# DIS06043H-ESP32-V2_020231204.net
KiCad netlist of a schematic drawn in EAGLE
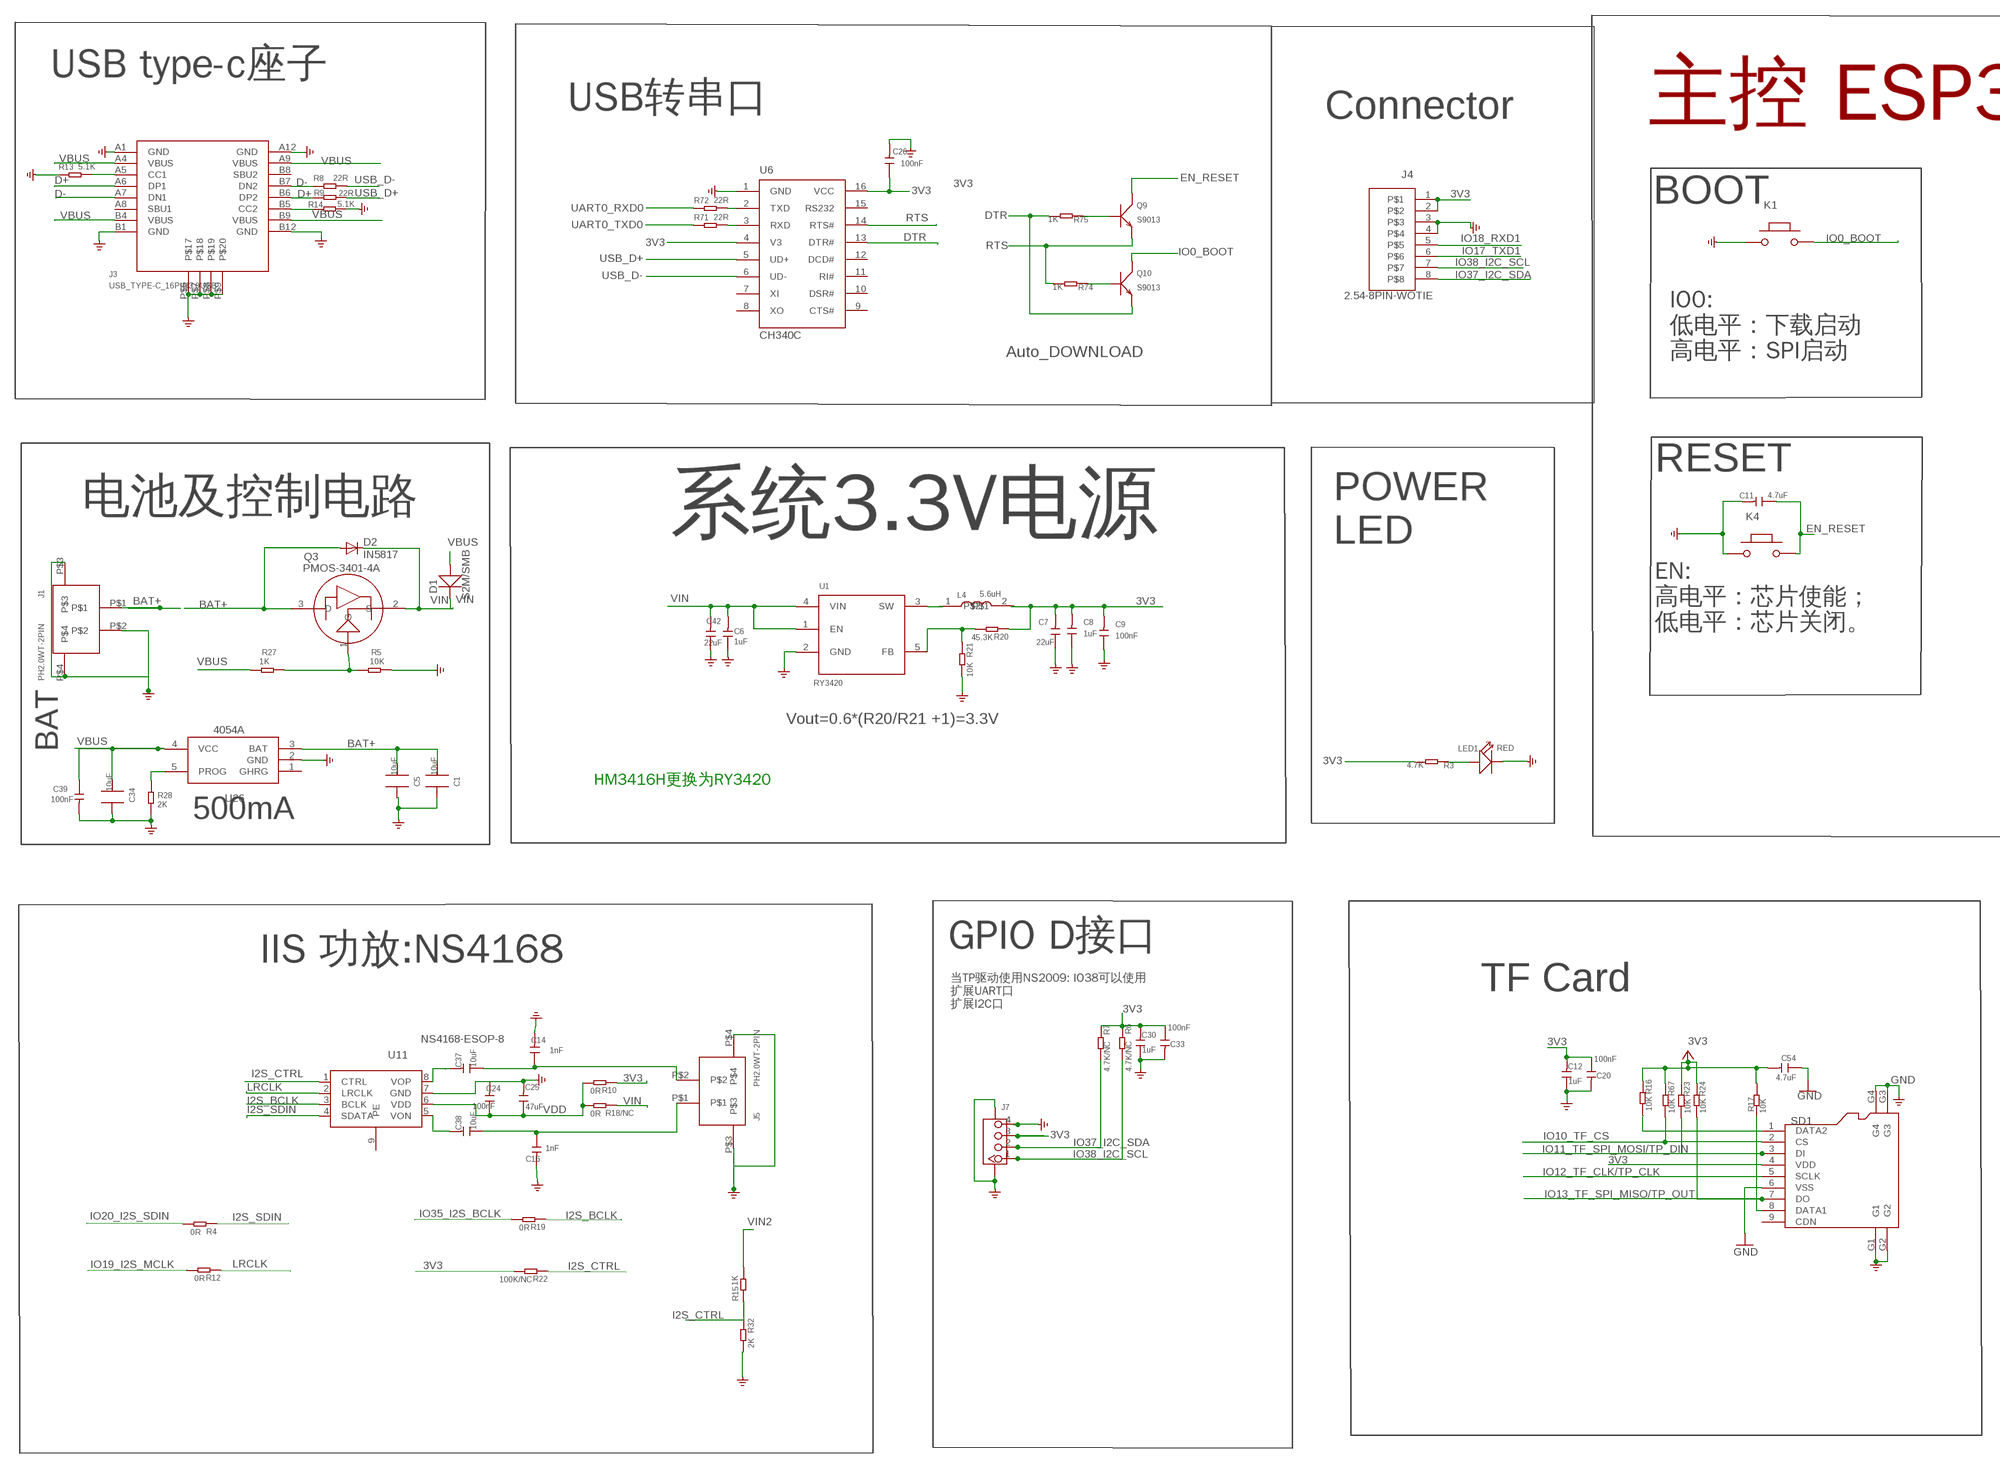
[diagram p0: schematic, sheet 1, part 1 of 2]
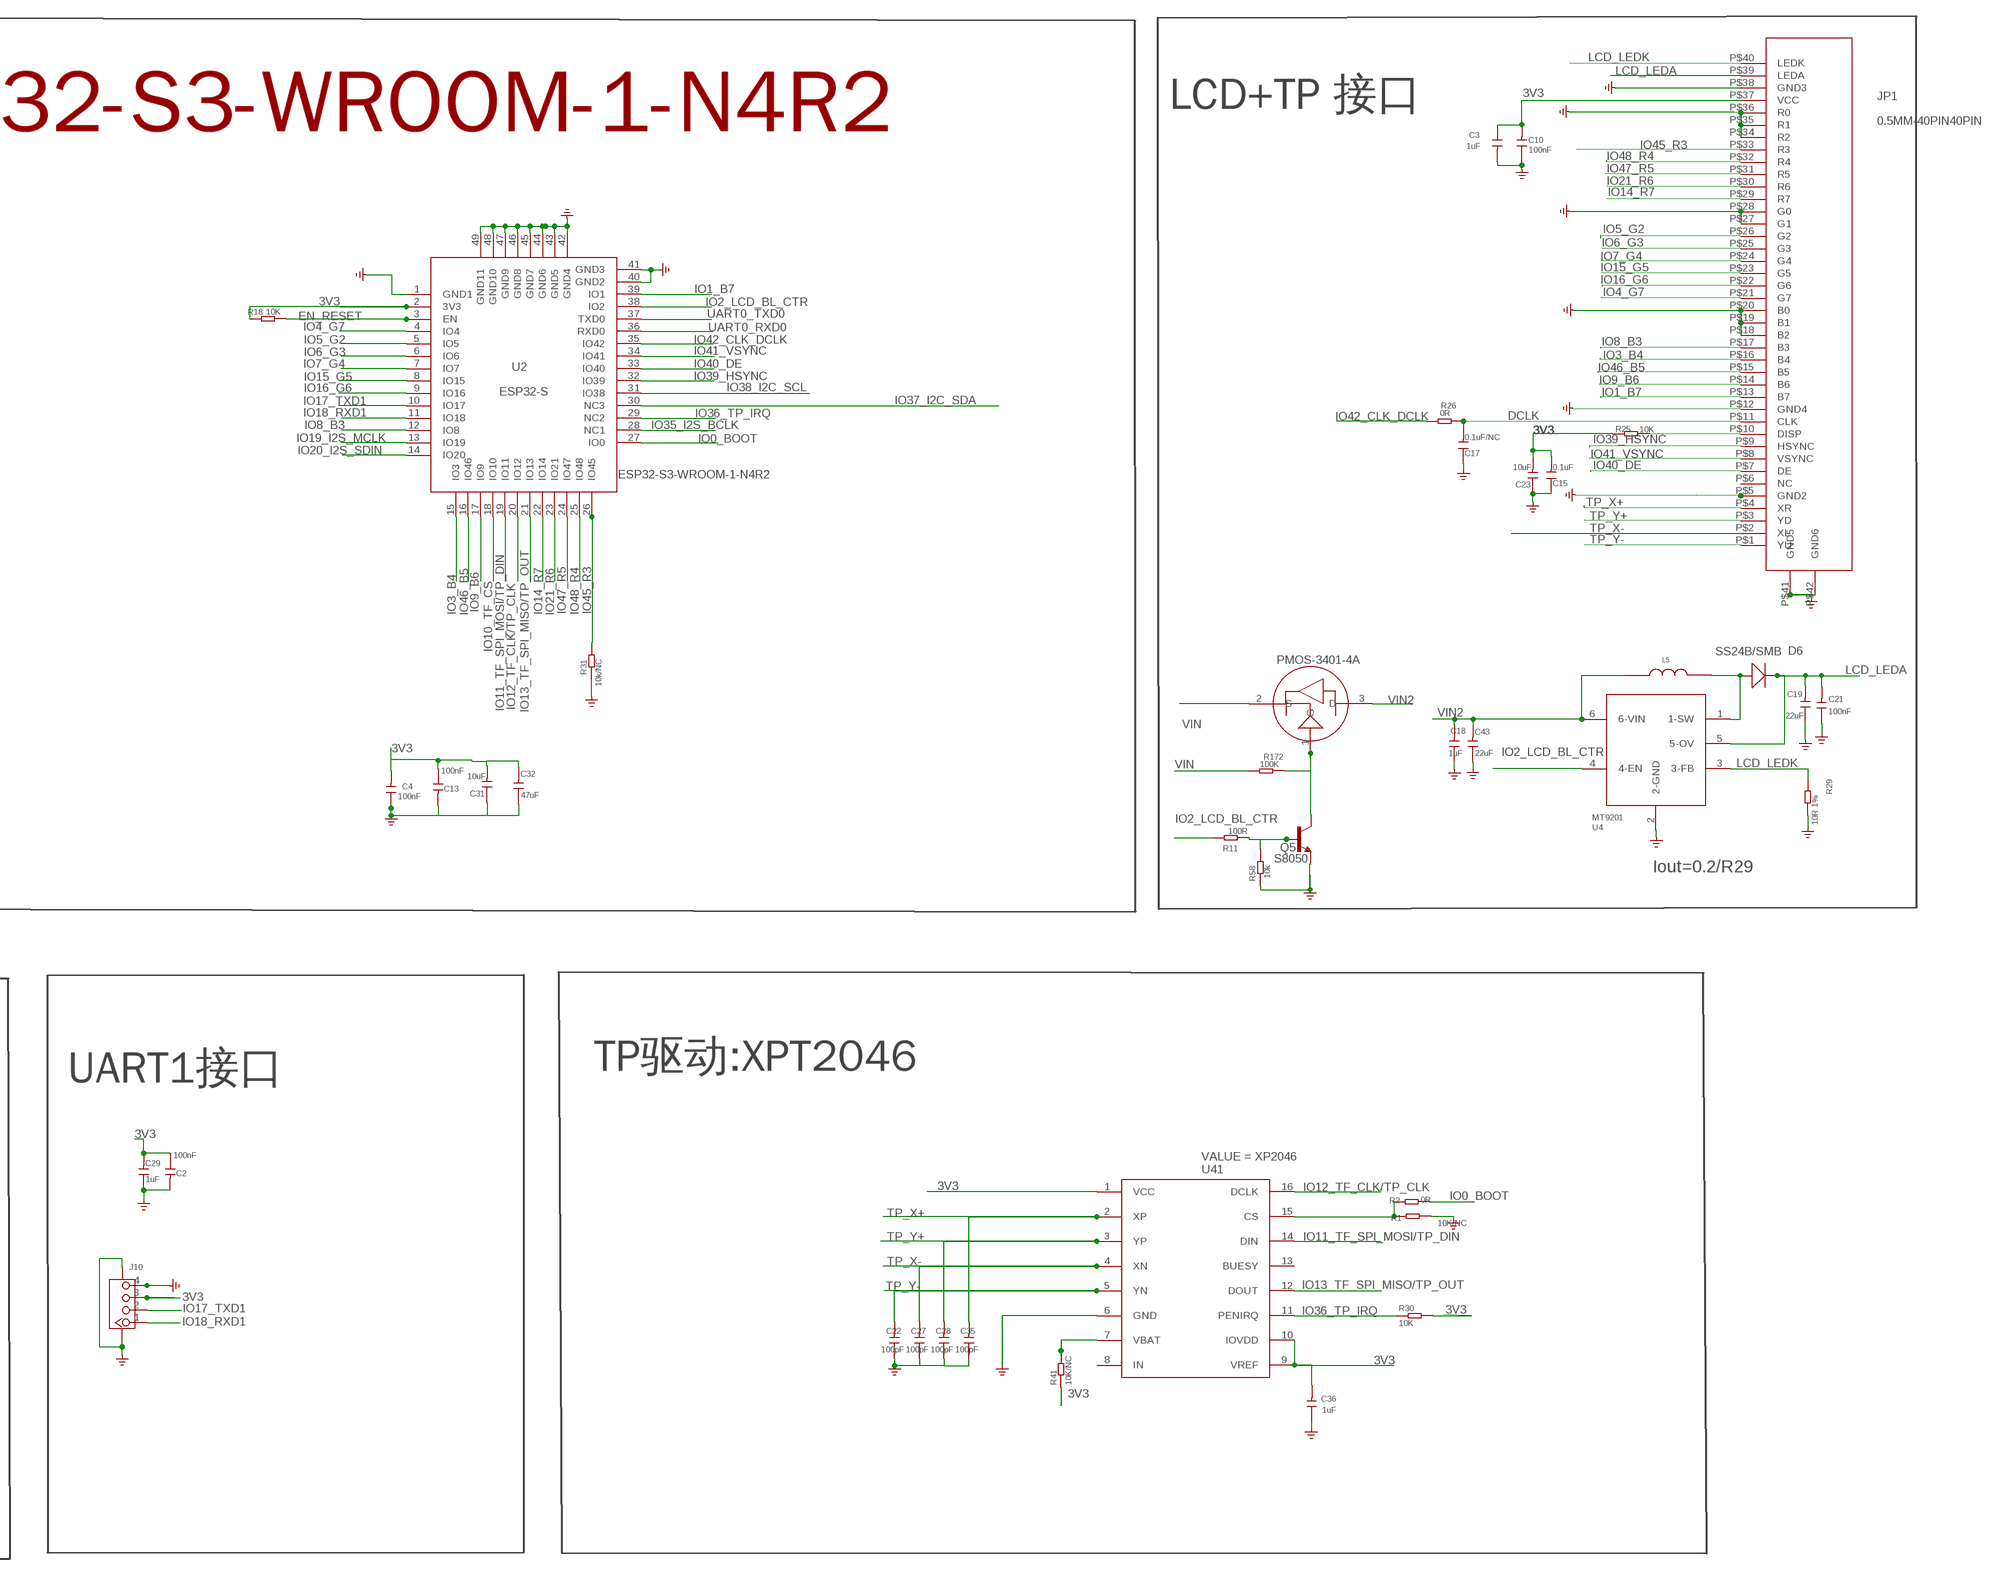
[diagram p1: schematic, sheet 1, part 2 of 2]

(export (version "E")
  (design (tool "Eeschema 10.0.6"))
  (components
    (comp (ref "C1")
      (value "10uF")
      (footprint "eagle-import:0805_S")
      (libsource (lib "eagle-import") (part "C0805_S"))
    )
    (comp (ref "C2")
      (value "100nF")
      (footprint "eagle-import:C0603")
      (libsource (lib "eagle-import") (part "C-0603"))
    )
    (comp (ref "C3")
      (value "1uF")
      (footprint "eagle-import:C0603")
      (libsource (lib "eagle-import") (part "C-0603"))
    )
    (comp (ref "C4")
      (value "100nF")
      (footprint "eagle-import:C0603")
      (libsource (lib "eagle-import") (part "C-0603"))
    )
    (comp (ref "C5")
      (value "10uF")
      (footprint "eagle-import:0805_S")
      (libsource (lib "eagle-import") (part "C0805_S"))
    )
    (comp (ref "C6")
      (value "1uF")
      (footprint "eagle-import:0603")
      (libsource (lib "eagle-import") (part "C0603"))
    )
    (comp (ref "C7")
      (value "22uF")
      (footprint "eagle-import:0805")
      (libsource (lib "eagle-import") (part "C0805"))
    )
    (comp (ref "C8")
      (value "1uF")
      (footprint "eagle-import:0603")
      (libsource (lib "eagle-import") (part "C0603"))
    )
    (comp (ref "C9")
      (value "100nF")
      (footprint "eagle-import:0603")
      (libsource (lib "eagle-import") (part "C0603"))
    )
    (comp (ref "C10")
      (value "100nF")
      (footprint "eagle-import:C0603")
      (libsource (lib "eagle-import") (part "C-0603"))
    )
    (comp (ref "C11")
      (value "4.7uF")
      (footprint "eagle-import:0603")
      (libsource (lib "eagle-import") (part "C0603"))
    )
    (comp (ref "C12")
      (value "1uF")
      (footprint "eagle-import:DISCRETE_C0603")
      (libsource (lib "eagle-import") (part "A_xbj_DISCRETE_C-0603"))
    )
    (comp (ref "C13")
      (value "100nF")
      (footprint "eagle-import:C0603")
      (libsource (lib "eagle-import") (part "C-0603"))
    )
    (comp (ref "C14")
      (value "1nF")
      (footprint "eagle-import:C0603")
      (libsource (lib "eagle-import") (part "C-0603"))
    )
    (comp (ref "C15")
      (value "0.1uF")
      (footprint "eagle-import:DISCRETE_C0603")
      (libsource (lib "eagle-import") (part "DISCRETE_C-0603"))
    )
    (comp (ref "C16")
      (value "1nF")
      (footprint "eagle-import:C0603")
      (libsource (lib "eagle-import") (part "C-0603"))
    )
    (comp (ref "C17")
      (value "0.1uF/NC")
      (footprint "eagle-import:DISCRETE_C0603")
      (libsource (lib "eagle-import") (part "DISCRETE_C-0603"))
    )
    (comp (ref "C18")
      (value "1uF")
      (footprint "eagle-import:0603")
      (libsource (lib "eagle-import") (part "C0603"))
    )
    (comp (ref "C19")
      (value "22uF")
      (footprint "eagle-import:0805")
      (libsource (lib "eagle-import") (part "C0805"))
    )
    (comp (ref "C20")
      (value "100nF")
      (footprint "eagle-import:C0603")
      (libsource (lib "eagle-import") (part "C-0603"))
    )
    (comp (ref "C21")
      (value "100nF")
      (footprint "eagle-import:0603")
      (libsource (lib "eagle-import") (part "C0603"))
    )
    (comp (ref "C22")
      (value "100pF")
      (footprint "eagle-import:0603")
      (libsource (lib "eagle-import") (part "C0603"))
    )
    (comp (ref "C23")
      (value "10uF")
      (footprint "eagle-import:DISCRETE_C0603")
      (libsource (lib "eagle-import") (part "DISCRETE_C-0603"))
    )
    (comp (ref "C24")
      (value "100nF")
      (footprint "eagle-import:C0603")
      (libsource (lib "eagle-import") (part "C-0603"))
    )
    (comp (ref "C25")
      (value "47uF")
      (footprint "eagle-import:0805")
      (libsource (lib "eagle-import") (part "C0805"))
    )
    (comp (ref "C26")
      (value "100nF")
      (footprint "eagle-import:0603")
      (libsource (lib "eagle-import") (part "C0603"))
    )
    (comp (ref "C27")
      (value "100pF")
      (footprint "eagle-import:0603")
      (libsource (lib "eagle-import") (part "C0603"))
    )
    (comp (ref "C28")
      (value "100pF")
      (footprint "eagle-import:0603")
      (libsource (lib "eagle-import") (part "C0603"))
    )
    (comp (ref "C29")
      (value "1uF")
      (footprint "eagle-import:DISCRETE_C0603")
      (libsource (lib "eagle-import") (part "A_xbj_DISCRETE_C-0603"))
    )
    (comp (ref "C30")
      (value "1uF")
      (footprint "eagle-import:DISCRETE_C0603")
      (libsource (lib "eagle-import") (part "A_xbj_DISCRETE_C-0603"))
    )
    (comp (ref "C31")
      (value "10uF")
      (footprint "eagle-import:DISCRETE_C0603")
      (libsource (lib "eagle-import") (part "DISCRETE_C-0603"))
    )
    (comp (ref "C32")
      (value "47uF")
      (footprint "eagle-import:0805")
      (libsource (lib "eagle-import") (part "C0805"))
    )
    (comp (ref "C33")
      (value "100nF")
      (footprint "eagle-import:C0603")
      (libsource (lib "eagle-import") (part "C-0603"))
    )
    (comp (ref "C34")
      (value "10uF")
      (footprint "eagle-import:0805_S")
      (libsource (lib "eagle-import") (part "C0805_S"))
    )
    (comp (ref "C35")
      (value "100pF")
      (footprint "eagle-import:0603")
      (libsource (lib "eagle-import") (part "C0603"))
    )
    (comp (ref "C36")
      (value "1uF")
      (footprint "eagle-import:DISCRETE_C0603")
      (libsource (lib "eagle-import") (part "A_xbj_DISCRETE_C-0603"))
    )
    (comp (ref "C37")
      (value "10uF")
      (footprint "eagle-import:DISCRETE_C0603")
      (libsource (lib "eagle-import") (part "A_xbj_DISCRETE_C-0603"))
    )
    (comp (ref "C38")
      (value "10uF")
      (footprint "eagle-import:DISCRETE_C0603")
      (libsource (lib "eagle-import") (part "A_xbj_DISCRETE_C-0603"))
    )
    (comp (ref "C39")
      (value "100nF")
      (footprint "eagle-import:C0603")
      (libsource (lib "eagle-import") (part "C-0603"))
    )
    (comp (ref "C42")
      (value "22uF")
      (footprint "eagle-import:0805")
      (libsource (lib "eagle-import") (part "C0805"))
    )
    (comp (ref "C43")
      (value "22uF")
      (footprint "eagle-import:0805")
      (libsource (lib "eagle-import") (part "C0805"))
    )
    (comp (ref "C54")
      (value "4.7uF")
      (footprint "eagle-import:DISCRETE_C0603")
      (libsource (lib "eagle-import") (part "DISCRETE_C-0603"))
    )
    (comp (ref "D1")
      (value "S2M/SMB")
      (footprint "eagle-import:214AB")
      (libsource (lib "eagle-import") (part "214ABDO-214AB"))
    )
    (comp (ref "D2")
      (value "IN5817")
      (footprint "eagle-import:DO-214AC")
      (libsource (lib "eagle-import") (part "DIODE-DO-214AC"))
    )
    (comp (ref "D6")
      (value "SS24B/SMB")
      (footprint "eagle-import:214AB")
      (libsource (lib "eagle-import") (part "214ABDO-214AB"))
    )
    (comp (ref "J1")
      (value "PH2.0WT-2PIN")
      (footprint "eagle-import:PH2.0WT-2PIN")
      (libsource (lib "eagle-import") (part "PH2.0WT-2PIN"))
    )
    (comp (ref "J3")
      (value "USB_TYPE-C_16PIN3.0USB")
      (footprint "eagle-import:KEVIN_3.0TYPEC-SMD")
      (libsource (lib "eagle-import") (part "USB_TYPE-C_16PIN3.0USB"))
    )
    (comp (ref "J4")
      (value "2.54-8PIN-WOTIE")
      (footprint "eagle-import:2.54-8P-WOTIE")
      (libsource (lib "eagle-import") (part "2.54-8PIN-WOTIE"))
    )
    (comp (ref "J5")
      (value "PH2.0WT-2PIN")
      (footprint "eagle-import:PH2.0WT-2PIN")
      (libsource (lib "eagle-import") (part "PH2.0WT-2PIN"))
    )
    (comp (ref "J7")
      (value "CONNECTOR_TWIG-4P-2.0-SMD-FEMALE-REINFORCE90D")
      (footprint "eagle-import:CONNECTOR_4P-SMD-2.0-90D")
      (libsource (lib "eagle-import") (part "CONNECTOR_TWIG-4P-2.0-SMD-FEMALE-REINFORCE90D"))
    )
    (comp (ref "J10")
      (value "CONNECTOR_TWIG-4P-2.0-SMD-FEMALE-REINFORCE90D")
      (footprint "eagle-import:CONNECTOR_4P-SMD-2.0-90D")
      (libsource (lib "eagle-import") (part "CONNECTOR_TWIG-4P-2.0-SMD-FEMALE-REINFORCE90D"))
    )
    (comp (ref "JP1")
      (value "0.5MM-40PIN40PIN")
      (footprint "eagle-import:0.5MM_40P")
      (libsource (lib "eagle-import") (part "0.5MM-40PIN40PIN"))
    )
    (comp (ref "K1")
      (value "BUTTON")
      (footprint "eagle-import:157SW")
      (libsource (lib "eagle-import") (part "PB157"))
    )
    (comp (ref "K4")
      (value "BUTTON")
      (footprint "eagle-import:157SW")
      (libsource (lib "eagle-import") (part "PB157"))
    )
    (comp (ref "L4")
      (value "5.6uH")
      (footprint "eagle-import:CD54_CD54")
      (libsource (lib "eagle-import") (part "L-0530"))
    )
    (comp (ref "L5")
      (value "CD32_6.8uH")
      (footprint "eagle-import:CD32")
      (libsource (lib "eagle-import") (part "CD32_950MA"))
    )
    (comp (ref "LED1")
      (value "RED")
      (footprint "eagle-import:DISCRETE_LED-0603")
      (libsource (lib "eagle-import") (part "DISCRETE_LED0603"))
    )
    (comp (ref "Q3")
      (value "PMOS-3401-4A")
      (footprint "eagle-import:SOT-23")
      (libsource (lib "eagle-import") (part "P-MOS-SOT23"))
    )
    (comp (ref "Q5")
      (value "S8050")
      (footprint "eagle-import:SPARKFUN_SOT23")
      (libsource (lib "eagle-import") (part "SPARKFUN_TRANSISTOR_NPNSOT23"))
    )
    (comp (ref "Q9")
      (value "S9013")
      (footprint "eagle-import:SOT23@1")
      (libsource (lib "eagle-import") (part "TRANSISTOR-NPN-SOT23"))
    )
    (comp (ref "Q10")
      (value "S9013")
      (footprint "eagle-import:SOT23@1")
      (libsource (lib "eagle-import") (part "TRANSISTOR-NPN-SOT23"))
    )
    (comp (ref "Q30")
      (value "PMOS-3401-4A")
      (footprint "eagle-import:SOT-23")
      (libsource (lib "eagle-import") (part "P-MOS-SOT23"))
    )
    (comp (ref "R1")
      (value "10K/NC")
      (footprint "eagle-import:R0603")
      (libsource (lib "eagle-import") (part "R0603"))
    )
    (comp (ref "R2")
      (value "0R")
      (footprint "eagle-import:DISCRETE_R0603")
      (libsource (lib "eagle-import") (part "Crowtail-_LED-V2.0-20190615-01_DISCRETE_R-0603"))
    )
    (comp (ref "R3")
      (value "4.7K")
      (footprint "eagle-import:DISCRETE_R0603")
      (libsource (lib "eagle-import") (part "Crowtail-_LED-V2.0-20190615-01_DISCRETE_R-0603"))
    )
    (comp (ref "R4")
      (value "0R")
      (footprint "eagle-import:DISCRETE_R0603")
      (libsource (lib "eagle-import") (part "Crowtail-_LED-V2.0-20190615-01_DISCRETE_R-0603"))
    )
    (comp (ref "R5")
      (value "10K")
      (footprint "eagle-import:DISCRETE_R0603")
      (libsource (lib "eagle-import") (part "DISCRETE_R-0603"))
    )
    (comp (ref "R6")
      (value "4.7K/NC")
      (footprint "eagle-import:DISCRETE_R0603")
      (libsource (lib "eagle-import") (part "Crowtail-_LED-V2.0-20190615-01_DISCRETE_R-0603"))
    )
    (comp (ref "R7")
      (value "4.7K/NC")
      (footprint "eagle-import:DISCRETE_R0603")
      (libsource (lib "eagle-import") (part "Crowtail-_LED-V2.0-20190615-01_DISCRETE_R-0603"))
    )
    (comp (ref "R8")
      (value "22R")
      (footprint "eagle-import:DISCRETE_R0603")
      (libsource (lib "eagle-import") (part "Crowtail-_LED-V2.0-20190615-01_DISCRETE_R-0603"))
    )
    (comp (ref "R9")
      (value "22R")
      (footprint "eagle-import:DISCRETE_R0603")
      (libsource (lib "eagle-import") (part "Crowtail-_LED-V2.0-20190615-01_DISCRETE_R-0603"))
    )
    (comp (ref "R10")
      (value "0R")
      (footprint "eagle-import:DISCRETE_R0603")
      (libsource (lib "eagle-import") (part "Crowtail-_LED-V2.0-20190615-01_DISCRETE_R-0603"))
    )
    (comp (ref "R11")
      (value "100R")
      (footprint "eagle-import:R0603")
      (libsource (lib "eagle-import") (part "R0603"))
    )
    (comp (ref "R12")
      (value "0R")
      (footprint "eagle-import:DISCRETE_R0603")
      (libsource (lib "eagle-import") (part "Crowtail-_LED-V2.0-20190615-01_DISCRETE_R-0603"))
    )
    (comp (ref "R13")
      (value "5.1K")
      (footprint "eagle-import:DISCRETE_R0603")
      (libsource (lib "eagle-import") (part "Crowtail-_LED-V2.0-20190615-01_DISCRETE_R-0603"))
    )
    (comp (ref "R14")
      (value "5.1K")
      (footprint "eagle-import:DISCRETE_R0603")
      (libsource (lib "eagle-import") (part "Crowtail-_LED-V2.0-20190615-01_DISCRETE_R-0603"))
    )
    (comp (ref "R15")
      (value "1K")
      (footprint "eagle-import:DISCRETE_R0603")
      (libsource (lib "eagle-import") (part "Crowtail-_LED-V2.0-20190615-01_DISCRETE_R-0603"))
    )
    (comp (ref "R16")
      (value "10K")
      (footprint "eagle-import:DISCRETE_R0603")
      (libsource (lib "eagle-import") (part "Crowtail-_LED-V2.0-20190615-01_DISCRETE_R-0603"))
    )
    (comp (ref "R17")
      (value "10K")
      (footprint "eagle-import:DISCRETE_R0603")
      (libsource (lib "eagle-import") (part "Crowtail-_LED-V2.0-20190615-01_DISCRETE_R-0603"))
    )
    (comp (ref "R18")
      (value "10K")
      (footprint "eagle-import:DISCRETE_R0603")
      (libsource (lib "eagle-import") (part "Crowtail-_LED-V2.0-20190615-01_DISCRETE_R-0603"))
    )
    (comp (ref "R18/NC")
      (value "0R")
      (footprint "eagle-import:DISCRETE_R0603")
      (libsource (lib "eagle-import") (part "Crowtail-_LED-V2.0-20190615-01_DISCRETE_R-0603"))
    )
    (comp (ref "R19")
      (value "0R")
      (footprint "eagle-import:DISCRETE_R0603")
      (libsource (lib "eagle-import") (part "Crowtail-_LED-V2.0-20190615-01_DISCRETE_R-0603"))
    )
    (comp (ref "R20")
      (value "45.3K")
      (footprint "eagle-import:DISCRETE_R0603")
      (libsource (lib "eagle-import") (part "Crowtail-_LED-V2.0-20190615-01_DISCRETE_R-0603"))
    )
    (comp (ref "R21")
      (value "10K")
      (footprint "eagle-import:DISCRETE_R0603")
      (libsource (lib "eagle-import") (part "Crowtail-_LED-V2.0-20190615-01_DISCRETE_R-0603"))
    )
    (comp (ref "R22")
      (value "100K/NC")
      (footprint "eagle-import:DISCRETE_R0603")
      (libsource (lib "eagle-import") (part "Crowtail-_LED-V2.0-20190615-01_DISCRETE_R-0603"))
    )
    (comp (ref "R23")
      (value "10K")
      (footprint "eagle-import:DISCRETE_R0603")
      (libsource (lib "eagle-import") (part "Crowtail-_LED-V2.0-20190615-01_DISCRETE_R-0603"))
    )
    (comp (ref "R24")
      (value "10K")
      (footprint "eagle-import:DISCRETE_R0603")
      (libsource (lib "eagle-import") (part "Crowtail-_LED-V2.0-20190615-01_DISCRETE_R-0603"))
    )
    (comp (ref "R25")
      (value "10K")
      (footprint "eagle-import:DISCRETE_R0603")
      (libsource (lib "eagle-import") (part "Crowtail-_LED-V2.0-20190615-01_DISCRETE_R-0603"))
    )
    (comp (ref "R26")
      (value "0R")
      (footprint "eagle-import:R0603")
      (libsource (lib "eagle-import") (part "R-0603"))
    )
    (comp (ref "R27")
      (value "1K")
      (footprint "eagle-import:DISCRETE_R0603")
      (libsource (lib "eagle-import") (part "DISCRETE_R-0603"))
    )
    (comp (ref "R28")
      (value "2K")
      (footprint "eagle-import:DISCRETE_R0603")
      (libsource (lib "eagle-import") (part "DISCRETE_R-0603"))
    )
    (comp (ref "R29")
      (value "10R 1%")
      (footprint "eagle-import:DISCRETE_R0603")
      (libsource (lib "eagle-import") (part "Crowtail-_LED-V2.0-20190615-01_DISCRETE_R-0603"))
    )
    (comp (ref "R30")
      (value "10K")
      (footprint "eagle-import:DISCRETE_R0603")
      (libsource (lib "eagle-import") (part "DISCRETE_R-0603"))
    )
    (comp (ref "R31")
      (value "10k/NC")
      (footprint "eagle-import:R0603")
      (libsource (lib "eagle-import") (part "R0603"))
    )
    (comp (ref "R32")
      (value "2K")
      (footprint "eagle-import:DISCRETE_R0603")
      (libsource (lib "eagle-import") (part "Crowtail-_LED-V2.0-20190615-01_DISCRETE_R-0603"))
    )
    (comp (ref "R41")
      (value "10K/NC")
      (footprint "eagle-import:DISCRETE_R0603")
      (libsource (lib "eagle-import") (part "DISCRETE_R-0603"))
    )
    (comp (ref "R58")
      (value "10k")
      (footprint "eagle-import:R0603")
      (libsource (lib "eagle-import") (part "R0603"))
    )
    (comp (ref "R67")
      (value "10K")
      (footprint "eagle-import:DISCRETE_R0603")
      (libsource (lib "eagle-import") (part "Crowtail-_LED-V2.0-20190615-01_DISCRETE_R-0603"))
    )
    (comp (ref "R71")
      (value "22R")
      (footprint "eagle-import:DISCRETE_R0603")
      (libsource (lib "eagle-import") (part "Crowtail-_LED-V2.0-20190615-01_DISCRETE_R-0603"))
    )
    (comp (ref "R72")
      (value "22R")
      (footprint "eagle-import:DISCRETE_R0603")
      (libsource (lib "eagle-import") (part "Crowtail-_LED-V2.0-20190615-01_DISCRETE_R-0603"))
    )
    (comp (ref "R74")
      (value "1K")
      (footprint "eagle-import:DISCRETE_R0603")
      (libsource (lib "eagle-import") (part "Crowtail-_LED-V2.0-20190615-01_DISCRETE_R-0603"))
    )
    (comp (ref "R75")
      (value "1K")
      (footprint "eagle-import:DISCRETE_R0603")
      (libsource (lib "eagle-import") (part "Crowtail-_LED-V2.0-20190615-01_DISCRETE_R-0603"))
    )
    (comp (ref "R172")
      (value "100K")
      (footprint "eagle-import:R0603")
      (libsource (lib "eagle-import") (part "R-0603"))
    )
    (comp (ref "SD1")
      (value "HOLDER-MICROSD-9P")
      (footprint "eagle-import:9P-SMD-W_-RING")
      (libsource (lib "eagle-import") (part "HOLDER-MICROSD-9P"))
    )
    (comp (ref "U1")
      (value "RY3420")
      (footprint "eagle-import:A_XBJ_SOT23-5")
      (libsource (lib "eagle-import") (part "A_XBJ_HM3420B"))
    )
    (comp (ref "U2")
      (value "ESP32-S")
      (footprint "eagle-import:ESP32-S3")
      (fields (field (name "U2") "ESP32-S3-WROOM-1-N4R2"))
      (libsource (lib "eagle-import") (part "ESP32-S"))
    )
    (comp (ref "U4")
      (value "MT9201")
      (footprint "eagle-import:SOT23-6")
      (libsource (lib "eagle-import") (part "MT9201"))
    )
    (comp (ref "U6")
      (value "CH340C")
      (footprint "eagle-import:SOP-16")
      (libsource (lib "eagle-import") (part "CH340G"))
    )
    (comp (ref "U11")
      (value "NS4168-ESOP-8")
      (footprint "eagle-import:NS4168-ESOP-8")
      (libsource (lib "eagle-import") (part "NS4168-ESOP-8"))
    )
    (comp (ref "U26")
      (value "4054A")
      (footprint "eagle-import:SOP23-5")
      (libsource (lib "eagle-import") (part "4054A"))
    )
    (comp (ref "U41")
      (value "XP2046")
      (footprint "eagle-import:XP2046-SSOP16")
      (libsource (lib "eagle-import") (part "XP2046"))
    )
  )
  (nets
    (net (code "1") (name "+3V3") (class "Default")
      (node (ref "C10") (pin "2") (pinfunction "2_2") (pintype "passive"))
      (node (ref "C12") (pin "2") (pinfunction "2_2") (pintype "passive"))
      (node (ref "C13") (pin "1") (pinfunction "1_1") (pintype "passive"))
      (node (ref "C15") (pin "2") (pinfunction "2_2") (pintype "passive"))
      (node (ref "C2") (pin "1") (pinfunction "1_1") (pintype "passive"))
      (node (ref "C20") (pin "1") (pinfunction "1_1") (pintype "passive"))
      (node (ref "C23") (pin "2") (pinfunction "2_2") (pintype "passive"))
      (node (ref "C26") (pin "1") (pinfunction "1_1") (pintype "passive"))
      (node (ref "C29") (pin "2") (pinfunction "2_2") (pintype "passive"))
      (node (ref "C3") (pin "1") (pinfunction "1_1") (pintype "passive"))
      (node (ref "C30") (pin "2") (pinfunction "2_2") (pintype "passive"))
      (node (ref "C31") (pin "2") (pinfunction "2_2") (pintype "passive"))
      (node (ref "C32") (pin "2") (pinfunction "2_2") (pintype "passive"))
      (node (ref "C33") (pin "1") (pinfunction "1_1") (pintype "passive"))
      (node (ref "C36") (pin "2") (pinfunction "2_2") (pintype "passive"))
      (node (ref "C4") (pin "2") (pinfunction "2_2") (pintype "passive"))
      (node (ref "C54") (pin "2") (pinfunction "2_2") (pintype "passive"))
      (node (ref "C7") (pin "2") (pinfunction "2_2") (pintype "passive"))
      (node (ref "C8") (pin "2") (pinfunction "2_2") (pintype "passive"))
      (node (ref "C9") (pin "2") (pinfunction "2_2") (pintype "passive"))
      (node (ref "J10") (pin "3") (pinfunction "3_3") (pintype "bidirectional"))
      (node (ref "J4") (pin "1") (pinfunction "P$1_1") (pintype "bidirectional"))
      (node (ref "J4") (pin "2") (pinfunction "P$2_2") (pintype "bidirectional"))
      (node (ref "J7") (pin "3") (pinfunction "3_3") (pintype "bidirectional"))
      (node (ref "JP1") (pin "P$37") (pinfunction "VCC_P$37") (pintype "bidirectional"))
      (node (ref "L4") (pin "2") (pinfunction "P$2_2") (pintype "bidirectional"))
      (node (ref "R10") (pin "1") (pinfunction "1_1") (pintype "passive"))
      (node (ref "R16") (pin "1") (pinfunction "1_1") (pintype "passive"))
      (node (ref "R17") (pin "1") (pinfunction "1_1") (pintype "passive"))
      (node (ref "R18") (pin "1") (pinfunction "1_1") (pintype "passive"))
      (node (ref "R20") (pin "1") (pinfunction "1_1") (pintype "passive"))
      (node (ref "R22") (pin "2") (pinfunction "2_2") (pintype "passive"))
      (node (ref "R23") (pin "1") (pinfunction "1_1") (pintype "passive"))
      (node (ref "R24") (pin "1") (pinfunction "1_1") (pintype "passive"))
      (node (ref "R25") (pin "1") (pinfunction "1_1") (pintype "passive"))
      (node (ref "R3") (pin "2") (pinfunction "2_2") (pintype "passive"))
      (node (ref "R30") (pin "2") (pinfunction "2_2") (pintype "passive"))
      (node (ref "R41") (pin "1") (pinfunction "1_1") (pintype "passive"))
      (node (ref "R6") (pin "1") (pinfunction "1_1") (pintype "passive"))
      (node (ref "R67") (pin "1") (pinfunction "1_1") (pintype "passive"))
      (node (ref "R7") (pin "1") (pinfunction "1_1") (pintype "passive"))
      (node (ref "SD1") (pin "4") (pinfunction "VDD_4") (pintype "bidirectional"))
      (node (ref "U2") (pin "2") (pinfunction "3V3_2") (pintype "bidirectional"))
      (node (ref "U41") (pin "1") (pinfunction "VCC_1") (pintype "bidirectional"))
      (node (ref "U41") (pin "10") (pinfunction "IOVDD_10") (pintype "bidirectional"))
      (node (ref "U41") (pin "9") (pinfunction "VREF_9") (pintype "bidirectional"))
      (node (ref "U6") (pin "16") (pinfunction "VCC_16") (pintype "bidirectional"))
      (node (ref "U6") (pin "4") (pinfunction "V3_4") (pintype "bidirectional"))
    )
    (net (code "2") (name "/BAT+") (class "Default")
      (node (ref "C1") (pin "2") (pinfunction "2_2") (pintype "bidirectional"))
      (node (ref "C5") (pin "2") (pinfunction "2_2") (pintype "bidirectional"))
      (node (ref "D2") (pin "A") (pinfunction "A_A") (pintype "passive"))
      (node (ref "J1") (pin "P$1") (pinfunction "P$1_P$1") (pintype "bidirectional"))
      (node (ref "Q3") (pin "3") (pinfunction "D_3") (pintype "bidirectional"))
      (node (ref "U26") (pin "3") (pinfunction "BAT_3") (pintype "bidirectional"))
    )
    (net (code "3") (name "/D+") (class "Default")
      (node (ref "J3") (pin "A6") (pinfunction "DP1_A6") (pintype "bidirectional"))
      (node (ref "J3") (pin "B6") (pinfunction "DP2_B6") (pintype "bidirectional"))
      (node (ref "R9") (pin "1") (pinfunction "1_1") (pintype "passive"))
    )
    (net (code "4") (name "/D-") (class "Default")
      (node (ref "J3") (pin "A7") (pinfunction "DN1_A7") (pintype "bidirectional"))
      (node (ref "J3") (pin "B7") (pinfunction "DN2_B7") (pintype "bidirectional"))
      (node (ref "R8") (pin "1") (pinfunction "1_1") (pintype "passive"))
    )
    (net (code "5") (name "/DCLK") (class "Default")
      (node (ref "C17") (pin "2") (pinfunction "2_2") (pintype "passive"))
      (node (ref "JP1") (pin "P$11") (pinfunction "CLK_P$11") (pintype "bidirectional"))
      (node (ref "R26") (pin "2") (pinfunction "2_2") (pintype "passive"))
    )
    (net (code "6") (name "/DTR") (class "Default")
      (node (ref "Q10") (pin "2") (pinfunction "E_2") (pintype "passive"))
      (node (ref "R75") (pin "2") (pinfunction "2_2") (pintype "passive"))
      (node (ref "U6") (pin "13") (pinfunction "DTR#_13") (pintype "bidirectional"))
    )
    (net (code "7") (name "/EN_RESET") (class "Default")
      (node (ref "C11") (pin "1") (pinfunction "1_1") (pintype "passive"))
      (node (ref "K4") (pin "2") (pinfunction "2_2") (pintype "passive"))
      (node (ref "Q9") (pin "3") (pinfunction "C_3") (pintype "passive"))
      (node (ref "R18") (pin "2") (pinfunction "2_2") (pintype "passive"))
      (node (ref "U2") (pin "3") (pinfunction "EN_3") (pintype "bidirectional"))
    )
    (net (code "8") (name "/I2S_BCLK") (class "Default")
      (node (ref "R19") (pin "1") (pinfunction "1_1") (pintype "passive"))
      (node (ref "U11") (pin "3") (pinfunction "BCLK_3") (pintype "bidirectional"))
    )
    (net (code "9") (name "/I2S_CTRL") (class "Default")
      (node (ref "R15") (pin "1") (pinfunction "1_1") (pintype "passive"))
      (node (ref "R22") (pin "1") (pinfunction "1_1") (pintype "passive"))
      (node (ref "R32") (pin "1") (pinfunction "1_1") (pintype "passive"))
      (node (ref "U11") (pin "1") (pinfunction "CTRL_1") (pintype "bidirectional"))
    )
    (net (code "10") (name "/I2S_SDIN") (class "Default")
      (node (ref "R4") (pin "1") (pinfunction "1_1") (pintype "passive"))
      (node (ref "U11") (pin "4") (pinfunction "SDATA_4") (pintype "bidirectional"))
    )
    (net (code "11") (name "/IO0_BOOT") (class "Default")
      (node (ref "K1") (pin "2") (pinfunction "2_2") (pintype "passive"))
      (node (ref "Q10") (pin "3") (pinfunction "C_3") (pintype "passive"))
      (node (ref "R2") (pin "1") (pinfunction "1_1") (pintype "passive"))
      (node (ref "U2") (pin "27") (pinfunction "IO0_27") (pintype "bidirectional"))
    )
    (net (code "12") (name "/IO1_B7") (class "Default")
      (node (ref "JP1") (pin "P$13") (pinfunction "B7_P$13") (pintype "bidirectional"))
      (node (ref "U2") (pin "39") (pinfunction "IO1_39") (pintype "bidirectional"))
    )
    (net (code "13") (name "/IO2_LCD_BL_CTR") (class "Default")
      (node (ref "R11") (pin "2") (pinfunction "2_2") (pintype "passive"))
      (node (ref "U2") (pin "38") (pinfunction "IO2_38") (pintype "bidirectional"))
      (node (ref "U4") (pin "4") (pinfunction "4-EN_4") (pintype "bidirectional"))
    )
    (net (code "14") (name "/IO3_B4") (class "Default")
      (node (ref "JP1") (pin "P$16") (pinfunction "B4_P$16") (pintype "bidirectional"))
      (node (ref "U2") (pin "15") (pinfunction "IO3_15") (pintype "bidirectional"))
    )
    (net (code "15") (name "/IO4_G7") (class "Default")
      (node (ref "JP1") (pin "P$21") (pinfunction "G7_P$21") (pintype "bidirectional"))
      (node (ref "U2") (pin "4") (pinfunction "IO4_4") (pintype "bidirectional"))
    )
    (net (code "16") (name "/IO5_G2") (class "Default")
      (node (ref "JP1") (pin "P$26") (pinfunction "G2_P$26") (pintype "bidirectional"))
      (node (ref "U2") (pin "5") (pinfunction "IO5_5") (pintype "bidirectional"))
    )
    (net (code "17") (name "/IO6_G3") (class "Default")
      (node (ref "JP1") (pin "P$25") (pinfunction "G3_P$25") (pintype "bidirectional"))
      (node (ref "U2") (pin "6") (pinfunction "IO6_6") (pintype "bidirectional"))
    )
    (net (code "18") (name "/IO7_G4") (class "Default")
      (node (ref "JP1") (pin "P$24") (pinfunction "G4_P$24") (pintype "bidirectional"))
      (node (ref "U2") (pin "7") (pinfunction "IO7_7") (pintype "bidirectional"))
    )
    (net (code "19") (name "/IO8_B3") (class "Default")
      (node (ref "JP1") (pin "P$17") (pinfunction "B3_P$17") (pintype "bidirectional"))
      (node (ref "U2") (pin "12") (pinfunction "IO8_12") (pintype "bidirectional"))
    )
    (net (code "20") (name "/IO9_B6") (class "Default")
      (node (ref "JP1") (pin "P$14") (pinfunction "B6_P$14") (pintype "bidirectional"))
      (node (ref "U2") (pin "17") (pinfunction "IO9_17") (pintype "bidirectional"))
    )
    (net (code "21") (name "/IO10_TF_CS") (class "Default")
      (node (ref "R67") (pin "2") (pinfunction "2_2") (pintype "passive"))
      (node (ref "SD1") (pin "2") (pinfunction "CS_2") (pintype "bidirectional"))
      (node (ref "U2") (pin "18") (pinfunction "IO10_18") (pintype "bidirectional"))
    )
    (net (code "22") (name "/IO11_TF_SPI_MOSI{slash}TP_DIN") (class "Default")
      (node (ref "R23") (pin "2") (pinfunction "2_2") (pintype "passive"))
      (node (ref "SD1") (pin "3") (pinfunction "DI_3") (pintype "bidirectional"))
      (node (ref "U2") (pin "19") (pinfunction "IO11_19") (pintype "bidirectional"))
      (node (ref "U41") (pin "14") (pinfunction "DIN_14") (pintype "bidirectional"))
    )
    (net (code "23") (name "/IO12_TF_CLK{slash}TP_CLK") (class "Default")
      (node (ref "SD1") (pin "5") (pinfunction "SCLK_5") (pintype "bidirectional"))
      (node (ref "U2") (pin "20") (pinfunction "IO12_20") (pintype "bidirectional"))
      (node (ref "U41") (pin "16") (pinfunction "DCLK_16") (pintype "bidirectional"))
    )
    (net (code "24") (name "/IO13_TF_SPI_MISO{slash}TP_OUT") (class "Default")
      (node (ref "R24") (pin "2") (pinfunction "2_2") (pintype "passive"))
      (node (ref "SD1") (pin "7") (pinfunction "DO_7") (pintype "bidirectional"))
      (node (ref "U2") (pin "21") (pinfunction "IO13_21") (pintype "bidirectional"))
      (node (ref "U41") (pin "12") (pinfunction "DOUT_12") (pintype "bidirectional"))
    )
    (net (code "25") (name "/IO14_R7") (class "Default")
      (node (ref "JP1") (pin "P$29") (pinfunction "R7_P$29") (pintype "bidirectional"))
      (node (ref "U2") (pin "22") (pinfunction "IO14_22") (pintype "bidirectional"))
    )
    (net (code "26") (name "/IO15_G5") (class "Default")
      (node (ref "JP1") (pin "P$23") (pinfunction "G5_P$23") (pintype "bidirectional"))
      (node (ref "U2") (pin "8") (pinfunction "IO15_8") (pintype "bidirectional"))
    )
    (net (code "27") (name "/IO16_G6") (class "Default")
      (node (ref "JP1") (pin "P$22") (pinfunction "G6_P$22") (pintype "bidirectional"))
      (node (ref "U2") (pin "9") (pinfunction "IO16_9") (pintype "bidirectional"))
    )
    (net (code "28") (name "/IO17_TXD1") (class "Default")
      (node (ref "J10") (pin "2") (pinfunction "2_2") (pintype "bidirectional"))
      (node (ref "J4") (pin "6") (pinfunction "P$6_6") (pintype "bidirectional"))
      (node (ref "U2") (pin "10") (pinfunction "IO17_10") (pintype "bidirectional"))
    )
    (net (code "29") (name "/IO18_RXD1") (class "Default")
      (node (ref "J10") (pin "1") (pinfunction "1_1") (pintype "bidirectional"))
      (node (ref "J4") (pin "5") (pinfunction "P$5_5") (pintype "bidirectional"))
      (node (ref "U2") (pin "11") (pinfunction "IO18_11") (pintype "bidirectional"))
    )
    (net (code "30") (name "/IO19_I2S_MCLK") (class "Default")
      (node (ref "R12") (pin "2") (pinfunction "2_2") (pintype "passive"))
      (node (ref "U2") (pin "13") (pinfunction "IO19_13") (pintype "bidirectional"))
    )
    (net (code "31") (name "/IO20_I2S_SDIN") (class "Default")
      (node (ref "R4") (pin "2") (pinfunction "2_2") (pintype "passive"))
      (node (ref "U2") (pin "14") (pinfunction "IO20_14") (pintype "bidirectional"))
    )
    (net (code "32") (name "/IO21_R6") (class "Default")
      (node (ref "JP1") (pin "P$30") (pinfunction "R6_P$30") (pintype "bidirectional"))
      (node (ref "U2") (pin "23") (pinfunction "IO21_23") (pintype "bidirectional"))
    )
    (net (code "33") (name "/IO35_I2S_BCLK") (class "Default")
      (node (ref "R19") (pin "2") (pinfunction "2_2") (pintype "passive"))
      (node (ref "U2") (pin "28") (pinfunction "NC1_28") (pintype "bidirectional"))
    )
    (net (code "34") (name "/IO36_TP_IRQ") (class "Default")
      (node (ref "R30") (pin "1") (pinfunction "1_1") (pintype "passive"))
      (node (ref "U2") (pin "29") (pinfunction "NC2_29") (pintype "bidirectional"))
      (node (ref "U41") (pin "11") (pinfunction "PENIRQ_11") (pintype "bidirectional"))
    )
    (net (code "35") (name "/IO37_I2C_SDA") (class "Default")
      (node (ref "J4") (pin "8") (pinfunction "P$8_8") (pintype "bidirectional"))
      (node (ref "J7") (pin "2") (pinfunction "2_2") (pintype "bidirectional"))
      (node (ref "R7") (pin "2") (pinfunction "2_2") (pintype "passive"))
      (node (ref "U2") (pin "30") (pinfunction "NC3_30") (pintype "bidirectional"))
    )
    (net (code "36") (name "/IO38_I2C_SCL") (class "Default")
      (node (ref "J4") (pin "7") (pinfunction "P$7_7") (pintype "bidirectional"))
      (node (ref "J7") (pin "1") (pinfunction "1_1") (pintype "bidirectional"))
      (node (ref "R6") (pin "2") (pinfunction "2_2") (pintype "passive"))
      (node (ref "U2") (pin "31") (pinfunction "IO38_31") (pintype "bidirectional"))
    )
    (net (code "37") (name "/IO39_HSYNC") (class "Default")
      (node (ref "JP1") (pin "P$9") (pinfunction "HSYNC_P$9") (pintype "bidirectional"))
      (node (ref "U2") (pin "32") (pinfunction "IO39_32") (pintype "bidirectional"))
    )
    (net (code "38") (name "/IO40_DE") (class "Default")
      (node (ref "JP1") (pin "P$7") (pinfunction "DE_P$7") (pintype "bidirectional"))
      (node (ref "U2") (pin "33") (pinfunction "IO40_33") (pintype "bidirectional"))
    )
    (net (code "39") (name "/IO41_VSYNC") (class "Default")
      (node (ref "JP1") (pin "P$8") (pinfunction "VSYNC_P$8") (pintype "bidirectional"))
      (node (ref "U2") (pin "34") (pinfunction "IO41_34") (pintype "bidirectional"))
    )
    (net (code "40") (name "/IO42_CLK_DCLK") (class "Default")
      (node (ref "R26") (pin "1") (pinfunction "1_1") (pintype "passive"))
      (node (ref "U2") (pin "35") (pinfunction "IO42_35") (pintype "bidirectional"))
    )
    (net (code "41") (name "/IO45_R3") (class "Default")
      (node (ref "JP1") (pin "P$33") (pinfunction "R3_P$33") (pintype "bidirectional"))
      (node (ref "R31") (pin "2") (pinfunction "2_2") (pintype "passive"))
      (node (ref "U2") (pin "26") (pinfunction "IO45_26") (pintype "bidirectional"))
    )
    (net (code "42") (name "/IO46_B5") (class "Default")
      (node (ref "JP1") (pin "P$15") (pinfunction "B5_P$15") (pintype "bidirectional"))
      (node (ref "U2") (pin "16") (pinfunction "IO46_16") (pintype "bidirectional"))
    )
    (net (code "43") (name "/IO47_R5") (class "Default")
      (node (ref "JP1") (pin "P$31") (pinfunction "R5_P$31") (pintype "bidirectional"))
      (node (ref "U2") (pin "24") (pinfunction "IO47_24") (pintype "bidirectional"))
    )
    (net (code "44") (name "/IO48_R4") (class "Default")
      (node (ref "JP1") (pin "P$32") (pinfunction "R4_P$32") (pintype "bidirectional"))
      (node (ref "U2") (pin "25") (pinfunction "IO48_25") (pintype "bidirectional"))
    )
    (net (code "45") (name "/LCD_LEDA") (class "Default")
      (node (ref "C19") (pin "2") (pinfunction "2_2") (pintype "passive"))
      (node (ref "C21") (pin "2") (pinfunction "2_2") (pintype "passive"))
      (node (ref "D6") (pin "2") (pinfunction "-_2") (pintype "passive"))
      (node (ref "JP1") (pin "P$39") (pinfunction "LEDA_P$39") (pintype "bidirectional"))
      (node (ref "U4") (pin "5") (pinfunction "5-OV_5") (pintype "bidirectional"))
    )
    (net (code "46") (name "/LCD_LEDK") (class "Default")
      (node (ref "JP1") (pin "P$40") (pinfunction "LEDK_P$40") (pintype "bidirectional"))
      (node (ref "R29") (pin "1") (pinfunction "1_1") (pintype "passive"))
      (node (ref "U4") (pin "3") (pinfunction "3-FB_3") (pintype "bidirectional"))
    )
    (net (code "47") (name "/LRCLK") (class "Default")
      (node (ref "R12") (pin "1") (pinfunction "1_1") (pintype "passive"))
      (node (ref "U11") (pin "2") (pinfunction "LRCLK_2") (pintype "bidirectional"))
    )
    (net (code "48") (name "/RTS") (class "Default")
      (node (ref "Q9") (pin "2") (pinfunction "E_2") (pintype "passive"))
      (node (ref "R74") (pin "2") (pinfunction "2_2") (pintype "passive"))
      (node (ref "U6") (pin "14") (pinfunction "RTS#_14") (pintype "bidirectional"))
    )
    (net (code "49") (name "/TP_X+") (class "Default")
      (node (ref "C35") (pin "2") (pinfunction "2_2") (pintype "passive"))
      (node (ref "JP1") (pin "P$4") (pinfunction "XR_P$4") (pintype "bidirectional"))
      (node (ref "U41") (pin "2") (pinfunction "XP_2") (pintype "bidirectional"))
    )
    (net (code "50") (name "/TP_X-") (class "Default")
      (node (ref "C27") (pin "2") (pinfunction "2_2") (pintype "passive"))
      (node (ref "JP1") (pin "P$2") (pinfunction "XL_P$2") (pintype "bidirectional"))
      (node (ref "U41") (pin "4") (pinfunction "XN_4") (pintype "bidirectional"))
    )
    (net (code "51") (name "/TP_Y+") (class "Default")
      (node (ref "C28") (pin "2") (pinfunction "2_2") (pintype "passive"))
      (node (ref "JP1") (pin "P$3") (pinfunction "YD_P$3") (pintype "bidirectional"))
      (node (ref "U41") (pin "3") (pinfunction "YP_3") (pintype "bidirectional"))
    )
    (net (code "52") (name "/TP_Y-") (class "Default")
      (node (ref "C22") (pin "2") (pinfunction "2_2") (pintype "passive"))
      (node (ref "JP1") (pin "P$1") (pinfunction "YU_P$1") (pintype "bidirectional"))
      (node (ref "U41") (pin "5") (pinfunction "YN_5") (pintype "bidirectional"))
    )
    (net (code "53") (name "/UART0_RXD0") (class "Default")
      (node (ref "R72") (pin "1") (pinfunction "1_1") (pintype "passive"))
      (node (ref "U2") (pin "36") (pinfunction "RXD0_36") (pintype "bidirectional"))
    )
    (net (code "54") (name "/UART0_TXD0") (class "Default")
      (node (ref "R71") (pin "1") (pinfunction "1_1") (pintype "passive"))
      (node (ref "U2") (pin "37") (pinfunction "TXD0_37") (pintype "bidirectional"))
    )
    (net (code "55") (name "/USB_D+") (class "Default")
      (node (ref "R9") (pin "2") (pinfunction "2_2") (pintype "passive"))
      (node (ref "U6") (pin "5") (pinfunction "UD+_5") (pintype "bidirectional"))
    )
    (net (code "56") (name "/USB_D-") (class "Default")
      (node (ref "R8") (pin "2") (pinfunction "2_2") (pintype "passive"))
      (node (ref "U6") (pin "6") (pinfunction "UD-_6") (pintype "bidirectional"))
    )
    (net (code "57") (name "/VBUS") (class "Default")
      (node (ref "C34") (pin "2") (pinfunction "2_2") (pintype "bidirectional"))
      (node (ref "C39") (pin "1") (pinfunction "1_1") (pintype "passive"))
      (node (ref "D1") (pin "1") (pinfunction "+_1") (pintype "passive"))
      (node (ref "J3") (pin "A4") (pinfunction "VBUS_A4") (pintype "bidirectional"))
      (node (ref "J3") (pin "A9") (pinfunction "VBUS_A9") (pintype "bidirectional"))
      (node (ref "J3") (pin "B4") (pinfunction "VBUS_B4") (pintype "bidirectional"))
      (node (ref "J3") (pin "B9") (pinfunction "VBUS_B9") (pintype "bidirectional"))
      (node (ref "R27") (pin "2") (pinfunction "2_2") (pintype "passive"))
      (node (ref "U26") (pin "4") (pinfunction "VCC_4") (pintype "bidirectional"))
    )
    (net (code "58") (name "/VDD") (class "Default")
      (node (ref "C24") (pin "1") (pinfunction "1_1") (pintype "passive"))
      (node (ref "C25") (pin "1") (pinfunction "1_1") (pintype "passive"))
      (node (ref "R10") (pin "2") (pinfunction "2_2") (pintype "passive"))
      (node (ref "R18/NC") (pin "2") (pinfunction "2_2") (pintype "passive"))
      (node (ref "U11") (pin "6") (pinfunction "VDD_6") (pintype "bidirectional"))
    )
    (net (code "59") (name "/VIN") (class "Default")
      (node (ref "C42") (pin "2") (pinfunction "2_2") (pintype "passive"))
      (node (ref "C6") (pin "2") (pinfunction "2_2") (pintype "passive"))
      (node (ref "D1") (pin "2") (pinfunction "-_2") (pintype "passive"))
      (node (ref "D2") (pin "C") (pinfunction "C_C") (pintype "passive"))
      (node (ref "Q3") (pin "2") (pinfunction "S_2") (pintype "bidirectional"))
      (node (ref "Q30") (pin "2") (pinfunction "S_2") (pintype "bidirectional"))
      (node (ref "R172") (pin "1") (pinfunction "1_1") (pintype "passive"))
      (node (ref "R18/NC") (pin "1") (pinfunction "1_1") (pintype "passive"))
      (node (ref "U1") (pin "1") (pinfunction "EN_1") (pintype "bidirectional"))
      (node (ref "U1") (pin "4") (pinfunction "VIN_4") (pintype "bidirectional"))
    )
    (net (code "60") (name "/VIN2") (class "Default")
      (node (ref "C18") (pin "2") (pinfunction "2_2") (pintype "passive"))
      (node (ref "C43") (pin "2") (pinfunction "2_2") (pintype "passive"))
      (node (ref "L5") (pin "1") (pinfunction "1_1") (pintype "bidirectional"))
      (node (ref "Q30") (pin "3") (pinfunction "D_3") (pintype "bidirectional"))
      (node (ref "R15") (pin "2") (pinfunction "2_2") (pintype "passive"))
      (node (ref "U4") (pin "6") (pinfunction "6-VIN_6") (pintype "bidirectional"))
    )
    (net (code "61") (name "GND") (class "Default")
      (node (ref "C1") (pin "1") (pinfunction "1_1") (pintype "bidirectional"))
      (node (ref "C10") (pin "1") (pinfunction "1_1") (pintype "passive"))
      (node (ref "C11") (pin "2") (pinfunction "2_2") (pintype "passive"))
      (node (ref "C12") (pin "1") (pinfunction "1_1") (pintype "passive"))
      (node (ref "C13") (pin "2") (pinfunction "2_2") (pintype "passive"))
      (node (ref "C14") (pin "2") (pinfunction "2_2") (pintype "passive"))
      (node (ref "C15") (pin "1") (pinfunction "1_1") (pintype "passive"))
      (node (ref "C16") (pin "2") (pinfunction "2_2") (pintype "passive"))
      (node (ref "C17") (pin "1") (pinfunction "1_1") (pintype "passive"))
      (node (ref "C18") (pin "1") (pinfunction "1_1") (pintype "passive"))
      (node (ref "C19") (pin "1") (pinfunction "1_1") (pintype "passive"))
      (node (ref "C2") (pin "2") (pinfunction "2_2") (pintype "passive"))
      (node (ref "C20") (pin "2") (pinfunction "2_2") (pintype "passive"))
      (node (ref "C21") (pin "1") (pinfunction "1_1") (pintype "passive"))
      (node (ref "C22") (pin "1") (pinfunction "1_1") (pintype "passive"))
      (node (ref "C23") (pin "1") (pinfunction "1_1") (pintype "passive"))
      (node (ref "C24") (pin "2") (pinfunction "2_2") (pintype "passive"))
      (node (ref "C25") (pin "2") (pinfunction "2_2") (pintype "passive"))
      (node (ref "C26") (pin "2") (pinfunction "2_2") (pintype "passive"))
      (node (ref "C27") (pin "1") (pinfunction "1_1") (pintype "passive"))
      (node (ref "C28") (pin "1") (pinfunction "1_1") (pintype "passive"))
      (node (ref "C29") (pin "1") (pinfunction "1_1") (pintype "passive"))
      (node (ref "C3") (pin "2") (pinfunction "2_2") (pintype "passive"))
      (node (ref "C30") (pin "1") (pinfunction "1_1") (pintype "passive"))
      (node (ref "C31") (pin "1") (pinfunction "1_1") (pintype "passive"))
      (node (ref "C32") (pin "1") (pinfunction "1_1") (pintype "passive"))
      (node (ref "C33") (pin "2") (pinfunction "2_2") (pintype "passive"))
      (node (ref "C34") (pin "1") (pinfunction "1_1") (pintype "bidirectional"))
      (node (ref "C35") (pin "1") (pinfunction "1_1") (pintype "passive"))
      (node (ref "C36") (pin "1") (pinfunction "1_1") (pintype "passive"))
      (node (ref "C39") (pin "2") (pinfunction "2_2") (pintype "passive"))
      (node (ref "C4") (pin "1") (pinfunction "1_1") (pintype "passive"))
      (node (ref "C42") (pin "1") (pinfunction "1_1") (pintype "passive"))
      (node (ref "C43") (pin "1") (pinfunction "1_1") (pintype "passive"))
      (node (ref "C5") (pin "1") (pinfunction "1_1") (pintype "bidirectional"))
      (node (ref "C54") (pin "1") (pinfunction "1_1") (pintype "passive"))
      (node (ref "C6") (pin "1") (pinfunction "1_1") (pintype "passive"))
      (node (ref "C7") (pin "1") (pinfunction "1_1") (pintype "passive"))
      (node (ref "C8") (pin "1") (pinfunction "1_1") (pintype "passive"))
      (node (ref "C9") (pin "1") (pinfunction "1_1") (pintype "passive"))
      (node (ref "J1") (pin "P$2") (pinfunction "P$2_P$2") (pintype "bidirectional"))
      (node (ref "J1") (pin "P$3") (pinfunction "P$3_P$3") (pintype "bidirectional"))
      (node (ref "J1") (pin "P$4") (pinfunction "P$4_P$4") (pintype "bidirectional"))
      (node (ref "J10") (pin "4") (pinfunction "4_4") (pintype "bidirectional"))
      (node (ref "J10") (pin "SS1") (pinfunction "SS1_SS1") (pintype "bidirectional"))
      (node (ref "J10") (pin "SS2") (pinfunction "SS2_SS2") (pintype "bidirectional"))
      (node (ref "J3") (pin "A1") (pinfunction "GND_A1") (pintype "bidirectional"))
      (node (ref "J3") (pin "A12") (pinfunction "GND_A12") (pintype "bidirectional"))
      (node (ref "J3") (pin "B1") (pinfunction "GND_B1") (pintype "bidirectional"))
      (node (ref "J3") (pin "B12") (pinfunction "GND_B12") (pintype "bidirectional"))
      (node (ref "J3") (pin "P$6") (pinfunction "P$17_P$6") (pintype "bidirectional"))
      (node (ref "J3") (pin "P$7") (pinfunction "P$18_P$7") (pintype "bidirectional"))
      (node (ref "J3") (pin "P$8") (pinfunction "P$19_P$8") (pintype "bidirectional"))
      (node (ref "J3") (pin "P$9") (pinfunction "P$20_P$9") (pintype "bidirectional"))
      (node (ref "J4") (pin "3") (pinfunction "P$3_3") (pintype "bidirectional"))
      (node (ref "J4") (pin "4") (pinfunction "P$4_4") (pintype "bidirectional"))
      (node (ref "J5") (pin "P$3") (pinfunction "P$3_P$3") (pintype "bidirectional"))
      (node (ref "J5") (pin "P$4") (pinfunction "P$4_P$4") (pintype "bidirectional"))
      (node (ref "J7") (pin "4") (pinfunction "4_4") (pintype "bidirectional"))
      (node (ref "J7") (pin "SS1") (pinfunction "SS1_SS1") (pintype "bidirectional"))
      (node (ref "J7") (pin "SS2") (pinfunction "SS2_SS2") (pintype "bidirectional"))
      (node (ref "JP1") (pin "P$12") (pinfunction "GND4_P$12") (pintype "bidirectional"))
      (node (ref "JP1") (pin "P$18") (pinfunction "B2_P$18") (pintype "bidirectional"))
      (node (ref "JP1") (pin "P$19") (pinfunction "B1_P$19") (pintype "bidirectional"))
      (node (ref "JP1") (pin "P$20") (pinfunction "B0_P$20") (pintype "bidirectional"))
      (node (ref "JP1") (pin "P$27") (pinfunction "G1_P$27") (pintype "bidirectional"))
      (node (ref "JP1") (pin "P$28") (pinfunction "G0_P$28") (pintype "bidirectional"))
      (node (ref "JP1") (pin "P$34") (pinfunction "R2_P$34") (pintype "bidirectional"))
      (node (ref "JP1") (pin "P$35") (pinfunction "R1_P$35") (pintype "bidirectional"))
      (node (ref "JP1") (pin "P$36") (pinfunction "R0_P$36") (pintype "bidirectional"))
      (node (ref "JP1") (pin "P$38") (pinfunction "GND3_P$38") (pintype "bidirectional"))
      (node (ref "JP1") (pin "P$41") (pinfunction "GND5_P$41") (pintype "bidirectional"))
      (node (ref "JP1") (pin "P$42") (pinfunction "GND6_P$42") (pintype "bidirectional"))
      (node (ref "JP1") (pin "P$5") (pinfunction "GND2_P$5") (pintype "bidirectional"))
      (node (ref "K1") (pin "1") (pinfunction "1_1") (pintype "passive"))
      (node (ref "K4") (pin "1") (pinfunction "1_1") (pintype "passive"))
      (node (ref "LED1") (pin "-") (pinfunction "-_-") (pintype "passive"))
      (node (ref "Q5") (pin "2") (pinfunction "E_2") (pintype "passive"))
      (node (ref "R1") (pin "1") (pinfunction "1_1") (pintype "passive"))
      (node (ref "R13") (pin "1") (pinfunction "1_1") (pintype "passive"))
      (node (ref "R14") (pin "2") (pinfunction "2_2") (pintype "passive"))
      (node (ref "R21") (pin "2") (pinfunction "2_2") (pintype "passive"))
      (node (ref "R28") (pin "2") (pinfunction "2_2") (pintype "passive"))
      (node (ref "R29") (pin "2") (pinfunction "2_2") (pintype "passive"))
      (node (ref "R31") (pin "1") (pinfunction "1_1") (pintype "passive"))
      (node (ref "R32") (pin "2") (pinfunction "2_2") (pintype "passive"))
      (node (ref "R5") (pin "1") (pinfunction "1_1") (pintype "passive"))
      (node (ref "R58") (pin "1") (pinfunction "1_1") (pintype "passive"))
      (node (ref "SD1") (pin "6") (pinfunction "VSS_6") (pintype "bidirectional"))
      (node (ref "SD1") (pin "G1") (pinfunction "G1_G1") (pintype "bidirectional"))
      (node (ref "SD1") (pin "G2") (pinfunction "G2_G2") (pintype "bidirectional"))
      (node (ref "SD1") (pin "G3") (pinfunction "G3_G3") (pintype "bidirectional"))
      (node (ref "SD1") (pin "G4") (pinfunction "G4_G4") (pintype "bidirectional"))
      (node (ref "U1") (pin "2") (pinfunction "GND_2") (pintype "bidirectional"))
      (node (ref "U11") (pin "7") (pinfunction "GND_7") (pintype "bidirectional"))
      (node (ref "U2") (pin "1") (pinfunction "GND1_1") (pintype "bidirectional"))
      (node (ref "U2") (pin "40") (pinfunction "GND2_40") (pintype "bidirectional"))
      (node (ref "U2") (pin "41") (pinfunction "GND3_41") (pintype "bidirectional"))
      (node (ref "U2") (pin "42") (pinfunction "GND4_42") (pintype "bidirectional"))
      (node (ref "U2") (pin "43") (pinfunction "GND5_43") (pintype "bidirectional"))
      (node (ref "U2") (pin "44") (pinfunction "GND6_44") (pintype "bidirectional"))
      (node (ref "U2") (pin "45") (pinfunction "GND7_45") (pintype "bidirectional"))
      (node (ref "U2") (pin "46") (pinfunction "GND8_46") (pintype "bidirectional"))
      (node (ref "U2") (pin "47") (pinfunction "GND9_47") (pintype "bidirectional"))
      (node (ref "U2") (pin "48") (pinfunction "GND10_48") (pintype "bidirectional"))
      (node (ref "U2") (pin "49") (pinfunction "GND11_49") (pintype "bidirectional"))
      (node (ref "U26") (pin "2") (pinfunction "GND_2") (pintype "bidirectional"))
      (node (ref "U4") (pin "2") (pinfunction "2-GND_2") (pintype "bidirectional"))
      (node (ref "U41") (pin "6") (pinfunction "GND_6") (pintype "bidirectional"))
      (node (ref "U6") (pin "1") (pinfunction "GND_1") (pintype "bidirectional"))
    )
    (net (code "62") (name "Net-(C14-Pad1)") (class "Default")
      (node (ref "C14") (pin "1") (pinfunction "1_1") (pintype "passive"))
      (node (ref "C37") (pin "1") (pinfunction "1_1") (pintype "passive"))
      (node (ref "J5") (pin "P$2") (pinfunction "P$2_P$2") (pintype "bidirectional"))
    )
    (net (code "63") (name "Net-(C16-Pad1)") (class "Default")
      (node (ref "C16") (pin "1") (pinfunction "1_1") (pintype "passive"))
      (node (ref "C38") (pin "1") (pinfunction "1_1") (pintype "passive"))
      (node (ref "J5") (pin "P$1") (pinfunction "P$1_P$1") (pintype "bidirectional"))
    )
    (net (code "64") (name "Net-(D6-+)") (class "Default")
      (node (ref "D6") (pin "1") (pinfunction "+_1") (pintype "passive"))
      (node (ref "L5") (pin "2") (pinfunction "2_2") (pintype "bidirectional"))
      (node (ref "U4") (pin "1") (pinfunction "1-SW_1") (pintype "bidirectional"))
    )
    (net (code "65") (name "Net-(J3-CC1)") (class "Default")
      (node (ref "J3") (pin "A5") (pinfunction "CC1_A5") (pintype "bidirectional"))
      (node (ref "R13") (pin "2") (pinfunction "2_2") (pintype "passive"))
    )
    (net (code "66") (name "Net-(J3-CC2)") (class "Default")
      (node (ref "J3") (pin "B5") (pinfunction "CC2_B5") (pintype "bidirectional"))
      (node (ref "R14") (pin "1") (pinfunction "1_1") (pintype "passive"))
    )
    (net (code "67") (name "Net-(JP1-DISP)") (class "Default")
      (node (ref "JP1") (pin "P$10") (pinfunction "DISP_P$10") (pintype "bidirectional"))
      (node (ref "R25") (pin "2") (pinfunction "2_2") (pintype "passive"))
    )
    (net (code "68") (name "Net-(L4-P$1)") (class "Default")
      (node (ref "L4") (pin "1") (pinfunction "P$1_1") (pintype "bidirectional"))
      (node (ref "U1") (pin "3") (pinfunction "SW_3") (pintype "bidirectional"))
    )
    (net (code "69") (name "Net-(LED1-Pad+)") (class "Default")
      (node (ref "LED1") (pin "+") (pinfunction "+_+") (pintype "passive"))
      (node (ref "R3") (pin "1") (pinfunction "1_1") (pintype "passive"))
    )
    (net (code "70") (name "Net-(Q3-G)") (class "Default")
      (node (ref "Q3") (pin "1") (pinfunction "G_1") (pintype "bidirectional"))
      (node (ref "R27") (pin "1") (pinfunction "1_1") (pintype "passive"))
      (node (ref "R5") (pin "2") (pinfunction "2_2") (pintype "passive"))
    )
    (net (code "71") (name "Net-(Q5-B)") (class "Default")
      (node (ref "Q5") (pin "1") (pinfunction "B_1") (pintype "passive"))
      (node (ref "R11") (pin "1") (pinfunction "1_1") (pintype "passive"))
      (node (ref "R58") (pin "2") (pinfunction "2_2") (pintype "passive"))
    )
    (net (code "72") (name "Net-(Q9-B)") (class "Default")
      (node (ref "Q9") (pin "1") (pinfunction "B_1") (pintype "passive"))
      (node (ref "R75") (pin "1") (pinfunction "1_1") (pintype "passive"))
    )
    (net (code "73") (name "Net-(Q10-B)") (class "Default")
      (node (ref "Q10") (pin "1") (pinfunction "B_1") (pintype "passive"))
      (node (ref "R74") (pin "1") (pinfunction "1_1") (pintype "passive"))
    )
    (net (code "74") (name "Net-(Q30-G)") (class "Default")
      (node (ref "Q30") (pin "1") (pinfunction "G_1") (pintype "bidirectional"))
      (node (ref "Q5") (pin "3") (pinfunction "C_3") (pintype "passive"))
      (node (ref "R172") (pin "2") (pinfunction "2_2") (pintype "passive"))
    )
    (net (code "75") (name "Net-(SD1-DATA1)") (class "Default")
      (node (ref "R17") (pin "2") (pinfunction "2_2") (pintype "passive"))
      (node (ref "SD1") (pin "8") (pinfunction "DATA1_8") (pintype "bidirectional"))
    )
    (net (code "76") (name "Net-(SD1-DATA2)") (class "Default")
      (node (ref "R16") (pin "2") (pinfunction "2_2") (pintype "passive"))
      (node (ref "SD1") (pin "1") (pinfunction "DATA2_1") (pintype "bidirectional"))
    )
    (net (code "77") (name "Net-(U1-FB)") (class "Default")
      (node (ref "R20") (pin "2") (pinfunction "2_2") (pintype "passive"))
      (node (ref "R21") (pin "1") (pinfunction "1_1") (pintype "passive"))
      (node (ref "U1") (pin "5") (pinfunction "FB_5") (pintype "bidirectional"))
    )
    (net (code "78") (name "Net-(U6-RXD)") (class "Default")
      (node (ref "R71") (pin "2") (pinfunction "2_2") (pintype "passive"))
      (node (ref "U6") (pin "3") (pinfunction "RXD_3") (pintype "bidirectional"))
    )
    (net (code "79") (name "Net-(U6-TXD)") (class "Default")
      (node (ref "R72") (pin "2") (pinfunction "2_2") (pintype "passive"))
      (node (ref "U6") (pin "2") (pinfunction "TXD_2") (pintype "bidirectional"))
    )
    (net (code "80") (name "Net-(U11-VON)") (class "Default")
      (node (ref "C38") (pin "2") (pinfunction "2_2") (pintype "passive"))
      (node (ref "U11") (pin "5") (pinfunction "VON_5") (pintype "bidirectional"))
    )
    (net (code "81") (name "Net-(U11-VOP)") (class "Default")
      (node (ref "C37") (pin "2") (pinfunction "2_2") (pintype "passive"))
      (node (ref "U11") (pin "8") (pinfunction "VOP_8") (pintype "bidirectional"))
    )
    (net (code "82") (name "Net-(U26-PROG)") (class "Default")
      (node (ref "R28") (pin "1") (pinfunction "1_1") (pintype "passive"))
      (node (ref "U26") (pin "5") (pinfunction "PROG_5") (pintype "bidirectional"))
    )
    (net (code "83") (name "Net-(U41-CS)") (class "Default")
      (node (ref "R1") (pin "2") (pinfunction "2_2") (pintype "passive"))
      (node (ref "R2") (pin "2") (pinfunction "2_2") (pintype "passive"))
      (node (ref "U41") (pin "15") (pinfunction "CS_15") (pintype "bidirectional"))
    )
    (net (code "84") (name "Net-(U41-VBAT)") (class "Default")
      (node (ref "R41") (pin "2") (pinfunction "2_2") (pintype "passive"))
      (node (ref "U41") (pin "7") (pinfunction "VBAT_7") (pintype "bidirectional"))
    )
    (net (code "85") (name "unconnected-(J3-SBU1-PadA8)") (class "Default")
      (node (ref "J3") (pin "A8") (pinfunction "SBU1_A8") (pintype "bidirectional"))
    )
    (net (code "86") (name "unconnected-(J3-SBU2-PadB8)") (class "Default")
      (node (ref "J3") (pin "B8") (pinfunction "SBU2_B8") (pintype "bidirectional"))
    )
    (net (code "87") (name "unconnected-(JP1-NC-PadP$6)") (class "Default")
      (node (ref "JP1") (pin "P$6") (pinfunction "NC_P$6") (pintype "bidirectional"))
    )
    (net (code "88") (name "unconnected-(SD1-CDN-Pad9)") (class "Default")
      (node (ref "SD1") (pin "9") (pinfunction "CDN_9") (pintype "bidirectional"))
    )
    (net (code "89") (name "unconnected-(U6-CTS#-Pad9)") (class "Default")
      (node (ref "U6") (pin "9") (pinfunction "CTS#_9") (pintype "bidirectional"))
    )
    (net (code "90") (name "unconnected-(U6-DCD#-Pad12)") (class "Default")
      (node (ref "U6") (pin "12") (pinfunction "DCD#_12") (pintype "bidirectional"))
    )
    (net (code "91") (name "unconnected-(U6-DSR#-Pad10)") (class "Default")
      (node (ref "U6") (pin "10") (pinfunction "DSR#_10") (pintype "bidirectional"))
    )
    (net (code "92") (name "unconnected-(U6-RI#-Pad11)") (class "Default")
      (node (ref "U6") (pin "11") (pinfunction "RI#_11") (pintype "bidirectional"))
    )
    (net (code "93") (name "unconnected-(U6-RS232-Pad15)") (class "Default")
      (node (ref "U6") (pin "15") (pinfunction "RS232_15") (pintype "bidirectional"))
    )
    (net (code "94") (name "unconnected-(U6-XI-Pad7)") (class "Default")
      (node (ref "U6") (pin "7") (pinfunction "XI_7") (pintype "bidirectional"))
    )
    (net (code "95") (name "unconnected-(U6-XO-Pad8)") (class "Default")
      (node (ref "U6") (pin "8") (pinfunction "XO_8") (pintype "bidirectional"))
    )
    (net (code "96") (name "unconnected-(U11-PE-Pad9)") (class "Default")
      (node (ref "U11") (pin "9") (pinfunction "PE_9") (pintype "bidirectional"))
    )
    (net (code "97") (name "unconnected-(U26-GHRG-Pad1)") (class "Default")
      (node (ref "U26") (pin "1") (pinfunction "GHRG_1") (pintype "bidirectional"))
    )
    (net (code "98") (name "unconnected-(U41-BUESY-Pad13)") (class "Default")
      (node (ref "U41") (pin "13") (pinfunction "BUESY_13") (pintype "bidirectional"))
    )
    (net (code "99") (name "unconnected-(U41-IN-Pad8)") (class "Default")
      (node (ref "U41") (pin "8") (pinfunction "IN_8") (pintype "bidirectional"))
    )
  )
)
